# MCU.net
KiCad netlist of a schematic drawn in Altium Designer
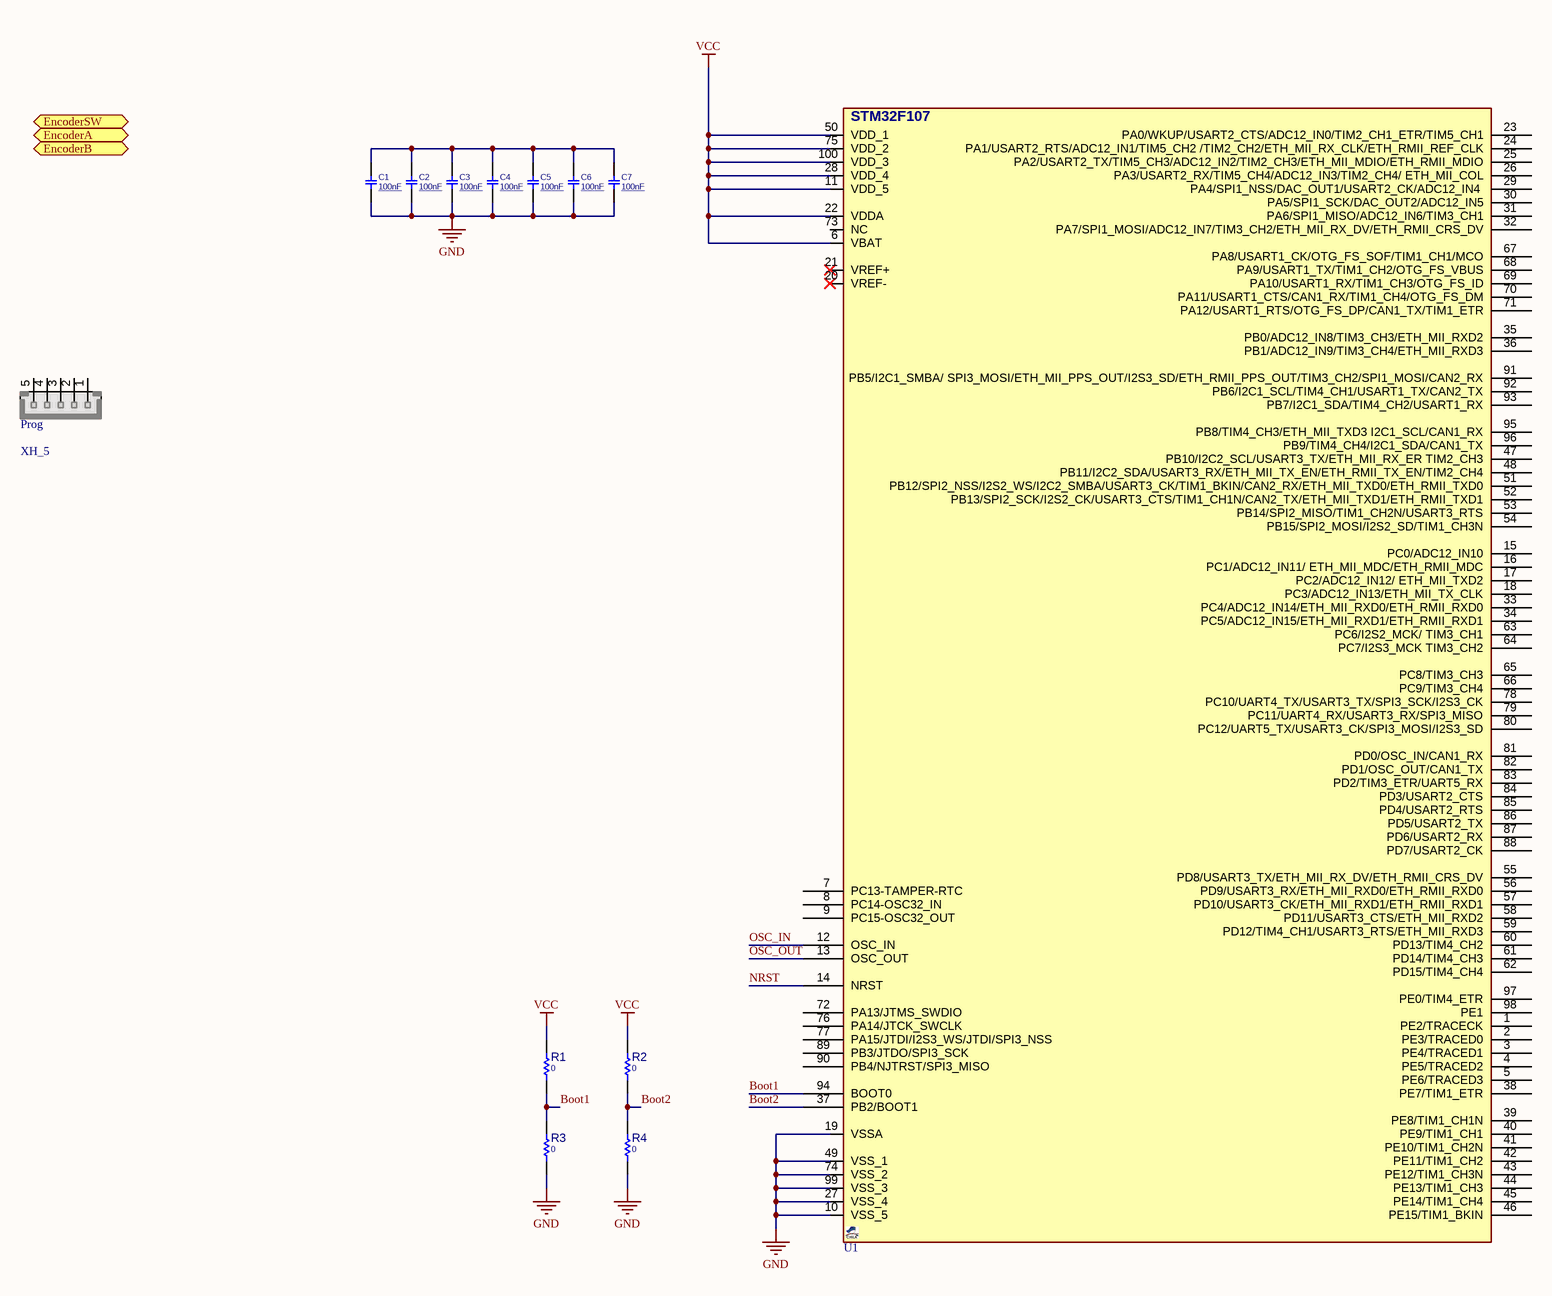
[diagram p0: MCU.SchDoc]

(export (version "E")
  (design (tool "Eeschema 10.0.6"))
  (components
    (comp (ref "C1")
      (value "100nF")
      (footprint "C0805")
      (description "CAP, MLCC, 100nF, 50V,0805")
      (fields (field (name "MANF_P#") "MANF_PART#"))
      (libsource (lib "passive_smd") (part "CAP_SMD_MLCC_0805"))
    )
    (comp (ref "C2")
      (value "100nF")
      (footprint "C0805")
      (description "CAP, MLCC, 100nF, 50V,0805")
      (fields (field (name "MANF_P#") "MANF_PART#"))
      (libsource (lib "passive_smd") (part "CAP_SMD_MLCC_0805"))
    )
    (comp (ref "C3")
      (value "100nF")
      (footprint "C0805")
      (description "CAP, MLCC, 100nF, 50V,0805")
      (fields (field (name "MANF_P#") "MANF_PART#"))
      (libsource (lib "passive_smd") (part "CAP_SMD_MLCC_0805"))
    )
    (comp (ref "C4")
      (value "100nF")
      (footprint "C0805")
      (description "CAP, MLCC, 100nF, 50V,0805")
      (fields (field (name "MANF_P#") "MANF_PART#"))
      (libsource (lib "passive_smd") (part "CAP_SMD_MLCC_0805"))
    )
    (comp (ref "C5")
      (value "100nF")
      (footprint "C0805")
      (description "CAP, MLCC, 100nF, 50V,0805")
      (fields (field (name "MANF_P#") "MANF_PART#"))
      (libsource (lib "passive_smd") (part "CAP_SMD_MLCC_0805"))
    )
    (comp (ref "C6")
      (value "100nF")
      (footprint "C0805")
      (description "CAP, MLCC, 100nF, 50V,0805")
      (fields (field (name "MANF_P#") "MANF_PART#"))
      (libsource (lib "passive_smd") (part "CAP_SMD_MLCC_0805"))
    )
    (comp (ref "C7")
      (value "100nF")
      (footprint "C0805")
      (description "CAP, MLCC, 100nF, 50V,0805")
      (fields (field (name "MANF_P#") "MANF_PART#"))
      (libsource (lib "passive_smd") (part "CAP_SMD_MLCC_0805"))
    )
    (comp (ref "Prog")
      (value "XH_5")
      (footprint "XH_5")
      (description "JST-XH pitch: 2.5mm")
      (fields (field (name "MANF_P#") "JST-B5B-XHA") (field (name "MANF") "JST"))
      (libsource (lib "conn_wire2board") (part "XH_5"))
    )
    (comp (ref "R1")
      (value "0")
      (footprint "R0805")
      (description "RESISTOR, SMD")
      (libsource (lib "passive_smd") (part "RES_SMD_0805"))
    )
    (comp (ref "R2")
      (value "0")
      (footprint "R0805")
      (description "RESISTOR, SMD")
      (libsource (lib "passive_smd") (part "RES_SMD_0805"))
    )
    (comp (ref "R3")
      (value "0")
      (footprint "R0805")
      (description "RESISTOR, SMD")
      (libsource (lib "passive_smd") (part "RES_SMD_0805"))
    )
    (comp (ref "R4")
      (value "0")
      (footprint "R0805")
      (description "RESISTOR, SMD")
      (libsource (lib "passive_smd") (part "RES_SMD_0805"))
    )
    (comp (ref "U1")
      (value "STM32F107")
      (footprint "QFG50_100")
      (description "MCU, STM32 ARM 32-bit, Cortex M3, 256KB FLASH, 64KB SRAM")
      (fields (field (name "MANF") "ST") (field (name "MANF_P#") "STM32F107VBT6"))
      (libsource (lib "mcu_stm32") (part "STM32F107VBT6_QFP100"))
    )
  )
  (nets
    (net (code "1") (name "/Boot1") (class "Default")
      (node (ref "R1") (pin "1") (pinfunction "1_1") (pintype "passive"))
      (node (ref "R3") (pin "2") (pinfunction "2_2") (pintype "passive"))
      (node (ref "U1") (pin "94") (pinfunction "BOOT0_94") (pintype "passive"))
    )
    (net (code "2") (name "/Boot2") (class "Default")
      (node (ref "R2") (pin "1") (pinfunction "1_1") (pintype "passive"))
      (node (ref "R4") (pin "2") (pinfunction "2_2") (pintype "passive"))
      (node (ref "U1") (pin "37") (pinfunction "PB2/BOOT1_37") (pintype "passive"))
    )
    (net (code "6") (name "/NRST") (class "Default")
      (node (ref "U1") (pin "14") (pinfunction "NRST_14") (pintype "passive"))
    )
    (net (code "7") (name "/OSC_IN") (class "Default")
      (node (ref "U1") (pin "12") (pinfunction "OSC_IN_12") (pintype "passive"))
    )
    (net (code "8") (name "/OSC_OUT") (class "Default")
      (node (ref "U1") (pin "13") (pinfunction "OSC_OUT_13") (pintype "passive"))
    )
    (net (code "9") (name "GND") (class "Default")
      (node (ref "C1") (pin "2") (pinfunction "2_2") (pintype "passive"))
      (node (ref "C2") (pin "2") (pinfunction "2_2") (pintype "passive"))
      (node (ref "C3") (pin "2") (pinfunction "2_2") (pintype "passive"))
      (node (ref "C4") (pin "2") (pinfunction "2_2") (pintype "passive"))
      (node (ref "C5") (pin "2") (pinfunction "2_2") (pintype "passive"))
      (node (ref "C6") (pin "2") (pinfunction "2_2") (pintype "passive"))
      (node (ref "C7") (pin "2") (pinfunction "2_2") (pintype "passive"))
      (node (ref "R3") (pin "1") (pinfunction "1_1") (pintype "passive"))
      (node (ref "R4") (pin "1") (pinfunction "1_1") (pintype "passive"))
      (node (ref "U1") (pin "10") (pinfunction "VSS_5_10") (pintype "passive"))
      (node (ref "U1") (pin "19") (pinfunction "VSSA_19") (pintype "passive"))
      (node (ref "U1") (pin "27") (pinfunction "VSS_4_27") (pintype "passive"))
      (node (ref "U1") (pin "49") (pinfunction "VSS_1_49") (pintype "passive"))
      (node (ref "U1") (pin "74") (pinfunction "VSS_2_74") (pintype "passive"))
      (node (ref "U1") (pin "99") (pinfunction "VSS_3_99") (pintype "passive"))
    )
    (net (code "10") (name "Net-(C1-Pad1)") (class "Default")
      (node (ref "C1") (pin "1") (pinfunction "1_1") (pintype "passive"))
      (node (ref "C2") (pin "1") (pinfunction "1_1") (pintype "passive"))
      (node (ref "C3") (pin "1") (pinfunction "1_1") (pintype "passive"))
      (node (ref "C4") (pin "1") (pinfunction "1_1") (pintype "passive"))
      (node (ref "C5") (pin "1") (pinfunction "1_1") (pintype "passive"))
      (node (ref "C6") (pin "1") (pinfunction "1_1") (pintype "passive"))
      (node (ref "C7") (pin "1") (pinfunction "1_1") (pintype "passive"))
    )
    (net (code "11") (name "VCC") (class "Default")
      (node (ref "R1") (pin "2") (pinfunction "2_2") (pintype "passive"))
      (node (ref "R2") (pin "2") (pinfunction "2_2") (pintype "passive"))
      (node (ref "U1") (pin "100") (pinfunction "VDD_3_100") (pintype "passive"))
      (node (ref "U1") (pin "11") (pinfunction "VDD_5_11") (pintype "passive"))
      (node (ref "U1") (pin "22") (pinfunction "VDDA_22") (pintype "passive"))
      (node (ref "U1") (pin "28") (pinfunction "VDD_4_28") (pintype "passive"))
      (node (ref "U1") (pin "50") (pinfunction "VDD_1_50") (pintype "passive"))
      (node (ref "U1") (pin "6") (pinfunction "VBAT_6") (pintype "passive"))
      (node (ref "U1") (pin "75") (pinfunction "VDD_2_75") (pintype "passive"))
    )
    (net (code "12") (name "unconnected-(Prog-Pad1)") (class "Default")
      (node (ref "Prog") (pin "1") (pinfunction "1_1") (pintype "passive"))
    )
    (net (code "13") (name "unconnected-(Prog-Pad2)") (class "Default")
      (node (ref "Prog") (pin "2") (pinfunction "2_2") (pintype "passive"))
    )
    (net (code "14") (name "unconnected-(Prog-Pad3)") (class "Default")
      (node (ref "Prog") (pin "3") (pinfunction "3_3") (pintype "passive"))
    )
    (net (code "15") (name "unconnected-(Prog-Pad4)") (class "Default")
      (node (ref "Prog") (pin "4") (pinfunction "4_4") (pintype "passive"))
    )
    (net (code "16") (name "unconnected-(Prog-Pad5)") (class "Default")
      (node (ref "Prog") (pin "5") (pinfunction "5_5") (pintype "passive"))
    )
    (net (code "17") (name "unconnected-(U1-NC-Pad73)") (class "Default")
      (node (ref "U1") (pin "73") (pinfunction "NC_73") (pintype "passive"))
    )
    (net (code "18") (name "unconnected-(U1-PA0{slash}WKUP{slash}USART2_CTS{slash}ADC12_IN0{slash}TIM2_CH1_ETR{slash}TIM5_CH1-Pad23)") (class "Default")
      (node (ref "U1") (pin "23") (pinfunction "PA0/WKUP/USART2_CTS/ADC12_IN0/TIM2_CH1_ETR/TIM5_CH1_23") (pintype "passive"))
    )
    (net (code "19") (name "unconnected-(U1-PA1{slash}USART2_RTS{slash}ADC12_IN1{slash}TIM5_CH2_{slash}TIM2_CH2{slash}ETH_MII_RX_CLK{slash}ETH_RMII_REF_CLK-Pad24)") (class "Default")
      (node (ref "U1") (pin "24") (pinfunction "PA1/USART2_RTS/ADC12_IN1/TIM5_CH2_/TIM2_CH2/ETH_MII_RX_CLK/ETH_RMII_REF_CLK_24") (pintype "passive"))
    )
    (net (code "20") (name "unconnected-(U1-PA2{slash}USART2_TX{slash}TIM5_CH3{slash}ADC12_IN2{slash}TIM2_CH3{slash}ETH_MII_MDIO{slash}ETH_RMII_MDIO-Pad25)") (class "Default")
      (node (ref "U1") (pin "25") (pinfunction "PA2/USART2_TX/TIM5_CH3/ADC12_IN2/TIM2_CH3/ETH_MII_MDIO/ETH_RMII_MDIO_25") (pintype "passive"))
    )
    (net (code "21") (name "unconnected-(U1-PA3{slash}USART2_RX{slash}TIM5_CH4{slash}ADC12_IN3{slash}TIM2_CH4{slash}_ETH_MII_COL-Pad26)") (class "Default")
      (node (ref "U1") (pin "26") (pinfunction "PA3/USART2_RX/TIM5_CH4/ADC12_IN3/TIM2_CH4/_ETH_MII_COL_26") (pintype "passive"))
    )
    (net (code "22") (name "unconnected-(U1-PA4{slash}SPI1_NSS{slash}DAC_OUT1{slash}USART2_CK{slash}ADC12_IN4-Pad29)") (class "Default")
      (node (ref "U1") (pin "29") (pinfunction "PA4/SPI1_NSS/DAC_OUT1/USART2_CK/ADC12_IN4_29") (pintype "passive"))
    )
    (net (code "23") (name "unconnected-(U1-PA5{slash}SPI1_SCK{slash}DAC_OUT2{slash}ADC12_IN5-Pad30)") (class "Default")
      (node (ref "U1") (pin "30") (pinfunction "PA5/SPI1_SCK/DAC_OUT2/ADC12_IN5_30") (pintype "passive"))
    )
    (net (code "24") (name "unconnected-(U1-PA6{slash}SPI1_MISO{slash}ADC12_IN6{slash}TIM3_CH1-Pad31)") (class "Default")
      (node (ref "U1") (pin "31") (pinfunction "PA6/SPI1_MISO/ADC12_IN6/TIM3_CH1_31") (pintype "passive"))
    )
    (net (code "25") (name "unconnected-(U1-PA7{slash}SPI1_MOSI{slash}ADC12_IN7{slash}TIM3_CH2{slash}ETH_MII_RX_DV{slash}ETH_RMII_CRS_DV-Pad32)") (class "Default")
      (node (ref "U1") (pin "32") (pinfunction "PA7/SPI1_MOSI/ADC12_IN7/TIM3_CH2/ETH_MII_RX_DV/ETH_RMII_CRS_DV_32") (pintype "passive"))
    )
    (net (code "26") (name "unconnected-(U1-PA8{slash}USART1_CK{slash}OTG_FS_SOF{slash}TIM1_CH1{slash}MCO-Pad67)") (class "Default")
      (node (ref "U1") (pin "67") (pinfunction "PA8/USART1_CK/OTG_FS_SOF/TIM1_CH1/MCO_67") (pintype "passive"))
    )
    (net (code "27") (name "unconnected-(U1-PA9{slash}USART1_TX{slash}TIM1_CH2{slash}OTG_FS_VBUS-Pad68)") (class "Default")
      (node (ref "U1") (pin "68") (pinfunction "PA9/USART1_TX/TIM1_CH2/OTG_FS_VBUS_68") (pintype "passive"))
    )
    (net (code "28") (name "unconnected-(U1-PA10{slash}USART1_RX{slash}TIM1_CH3{slash}OTG_FS_ID-Pad69)") (class "Default")
      (node (ref "U1") (pin "69") (pinfunction "PA10/USART1_RX/TIM1_CH3/OTG_FS_ID_69") (pintype "passive"))
    )
    (net (code "29") (name "unconnected-(U1-PA11{slash}USART1_CTS{slash}CAN1_RX{slash}TIM1_CH4{slash}OTG_FS_DM-Pad70)") (class "Default")
      (node (ref "U1") (pin "70") (pinfunction "PA11/USART1_CTS/CAN1_RX/TIM1_CH4/OTG_FS_DM_70") (pintype "passive"))
    )
    (net (code "30") (name "unconnected-(U1-PA12{slash}USART1_RTS{slash}OTG_FS_DP{slash}CAN1_TX{slash}TIM1_ETR-Pad71)") (class "Default")
      (node (ref "U1") (pin "71") (pinfunction "PA12/USART1_RTS/OTG_FS_DP/CAN1_TX/TIM1_ETR_71") (pintype "passive"))
    )
    (net (code "31") (name "unconnected-(U1-PA13{slash}JTMS_SWDIO-Pad72)") (class "Default")
      (node (ref "U1") (pin "72") (pinfunction "PA13/JTMS_SWDIO_72") (pintype "passive"))
    )
    (net (code "32") (name "unconnected-(U1-PA14{slash}JTCK_SWCLK-Pad76)") (class "Default")
      (node (ref "U1") (pin "76") (pinfunction "PA14/JTCK_SWCLK_76") (pintype "passive"))
    )
    (net (code "33") (name "unconnected-(U1-PA15{slash}JTDI{slash}I2S3_WS{slash}JTDI{slash}SPI3_NSS-Pad77)") (class "Default")
      (node (ref "U1") (pin "77") (pinfunction "PA15/JTDI/I2S3_WS/JTDI/SPI3_NSS_77") (pintype "passive"))
    )
    (net (code "34") (name "unconnected-(U1-PB0{slash}ADC12_IN8{slash}TIM3_CH3{slash}ETH_MII_RXD2-Pad35)") (class "Default")
      (node (ref "U1") (pin "35") (pinfunction "PB0/ADC12_IN8/TIM3_CH3/ETH_MII_RXD2_35") (pintype "passive"))
    )
    (net (code "35") (name "unconnected-(U1-PB1{slash}ADC12_IN9{slash}TIM3_CH4{slash}ETH_MII_RXD3-Pad36)") (class "Default")
      (node (ref "U1") (pin "36") (pinfunction "PB1/ADC12_IN9/TIM3_CH4/ETH_MII_RXD3_36") (pintype "passive"))
    )
    (net (code "36") (name "unconnected-(U1-PB3{slash}JTDO{slash}SPI3_SCK-Pad89)") (class "Default")
      (node (ref "U1") (pin "89") (pinfunction "PB3/JTDO/SPI3_SCK_89") (pintype "passive"))
    )
    (net (code "37") (name "unconnected-(U1-PB4{slash}NJTRST{slash}SPI3_MISO-Pad90)") (class "Default")
      (node (ref "U1") (pin "90") (pinfunction "PB4/NJTRST/SPI3_MISO_90") (pintype "passive"))
    )
    (net (code "38") (name "unconnected-(U1-PB5{slash}I2C1_SMBA{slash}_SPI3_MOSI{slash}ETH_MII_PPS_OUT{slash}I2S3_SD{slash}ETH_RMII_PPS_OUT{slash}TIM3_CH2{slash}SPI1_MOSI{slash}CAN2_RX-Pad91)") (class "Default")
      (node (ref "U1") (pin "91") (pinfunction "PB5/I2C1_SMBA/_SPI3_MOSI/ETH_MII_PPS_OUT/I2S3_SD/ETH_RMII_PPS_OUT/TIM3_CH2/SPI1_MOSI/CAN2_RX_91") (pintype "passive"))
    )
    (net (code "39") (name "unconnected-(U1-PB6{slash}I2C1_SCL{slash}TIM4_CH1{slash}USART1_TX{slash}CAN2_TX-Pad92)") (class "Default")
      (node (ref "U1") (pin "92") (pinfunction "PB6/I2C1_SCL/TIM4_CH1/USART1_TX/CAN2_TX_92") (pintype "passive"))
    )
    (net (code "40") (name "unconnected-(U1-PB7{slash}I2C1_SDA{slash}TIM4_CH2{slash}USART1_RX-Pad93)") (class "Default")
      (node (ref "U1") (pin "93") (pinfunction "PB7/I2C1_SDA/TIM4_CH2/USART1_RX_93") (pintype "passive"))
    )
    (net (code "41") (name "unconnected-(U1-PB8{slash}TIM4_CH3{slash}ETH_MII_TXD3_I2C1_SCL{slash}CAN1_RX-Pad95)") (class "Default")
      (node (ref "U1") (pin "95") (pinfunction "PB8/TIM4_CH3/ETH_MII_TXD3_I2C1_SCL/CAN1_RX_95") (pintype "passive"))
    )
    (net (code "42") (name "unconnected-(U1-PB9{slash}TIM4_CH4{slash}I2C1_SDA{slash}CAN1_TX-Pad96)") (class "Default")
      (node (ref "U1") (pin "96") (pinfunction "PB9/TIM4_CH4/I2C1_SDA/CAN1_TX_96") (pintype "passive"))
    )
    (net (code "43") (name "unconnected-(U1-PB10{slash}I2C2_SCL{slash}USART3_TX{slash}ETH_MII_RX_ER_TIM2_CH3-Pad47)") (class "Default")
      (node (ref "U1") (pin "47") (pinfunction "PB10/I2C2_SCL/USART3_TX/ETH_MII_RX_ER_TIM2_CH3_47") (pintype "passive"))
    )
    (net (code "44") (name "unconnected-(U1-PB11{slash}I2C2_SDA{slash}USART3_RX{slash}ETH_MII_TX_EN{slash}ETH_RMII_TX_EN{slash}TIM2_CH4-Pad48)") (class "Default")
      (node (ref "U1") (pin "48") (pinfunction "PB11/I2C2_SDA/USART3_RX/ETH_MII_TX_EN/ETH_RMII_TX_EN/TIM2_CH4_48") (pintype "passive"))
    )
    (net (code "45") (name "unconnected-(U1-PB12{slash}SPI2_NSS{slash}I2S2_WS{slash}I2C2_SMBA{slash}USART3_CK{slash}TIM1_BKIN{slash}CAN2_RX{slash}ETH_MII_TXD0{slash}ETH_RMII_TXD0-Pad51)") (class "Default")
      (node (ref "U1") (pin "51") (pinfunction "PB12/SPI2_NSS/I2S2_WS/I2C2_SMBA/USART3_CK/TIM1_BKIN/CAN2_RX/ETH_MII_TXD0/ETH_RMII_TXD0_51") (pintype "passive"))
    )
    (net (code "46") (name "unconnected-(U1-PB13{slash}SPI2_SCK{slash}I2S2_CK{slash}USART3_CTS{slash}TIM1_CH1N{slash}CAN2_TX{slash}ETH_MII_TXD1{slash}ETH_RMII_TXD1-Pad52)") (class "Default")
      (node (ref "U1") (pin "52") (pinfunction "PB13/SPI2_SCK/I2S2_CK/USART3_CTS/TIM1_CH1N/CAN2_TX/ETH_MII_TXD1/ETH_RMII_TXD1_52") (pintype "passive"))
    )
    (net (code "47") (name "unconnected-(U1-PB14{slash}SPI2_MISO{slash}TIM1_CH2N{slash}USART3_RTS-Pad53)") (class "Default")
      (node (ref "U1") (pin "53") (pinfunction "PB14/SPI2_MISO/TIM1_CH2N/USART3_RTS_53") (pintype "passive"))
    )
    (net (code "48") (name "unconnected-(U1-PB15{slash}SPI2_MOSI{slash}I2S2_SD{slash}TIM1_CH3N-Pad54)") (class "Default")
      (node (ref "U1") (pin "54") (pinfunction "PB15/SPI2_MOSI/I2S2_SD/TIM1_CH3N_54") (pintype "passive"))
    )
    (net (code "49") (name "unconnected-(U1-PC0{slash}ADC12_IN10-Pad15)") (class "Default")
      (node (ref "U1") (pin "15") (pinfunction "PC0/ADC12_IN10_15") (pintype "passive"))
    )
    (net (code "50") (name "unconnected-(U1-PC1{slash}ADC12_IN11{slash}_ETH_MII_MDC{slash}ETH_RMII_MDC-Pad16)") (class "Default")
      (node (ref "U1") (pin "16") (pinfunction "PC1/ADC12_IN11/_ETH_MII_MDC/ETH_RMII_MDC_16") (pintype "passive"))
    )
    (net (code "51") (name "unconnected-(U1-PC2{slash}ADC12_IN12{slash}_ETH_MII_TXD2-Pad17)") (class "Default")
      (node (ref "U1") (pin "17") (pinfunction "PC2/ADC12_IN12/_ETH_MII_TXD2_17") (pintype "passive"))
    )
    (net (code "52") (name "unconnected-(U1-PC3{slash}ADC12_IN13{slash}ETH_MII_TX_CLK-Pad18)") (class "Default")
      (node (ref "U1") (pin "18") (pinfunction "PC3/ADC12_IN13/ETH_MII_TX_CLK_18") (pintype "passive"))
    )
    (net (code "53") (name "unconnected-(U1-PC4{slash}ADC12_IN14{slash}ETH_MII_RXD0{slash}ETH_RMII_RXD0-Pad33)") (class "Default")
      (node (ref "U1") (pin "33") (pinfunction "PC4/ADC12_IN14/ETH_MII_RXD0/ETH_RMII_RXD0_33") (pintype "passive"))
    )
    (net (code "54") (name "unconnected-(U1-PC5{slash}ADC12_IN15{slash}ETH_MII_RXD1{slash}ETH_RMII_RXD1-Pad34)") (class "Default")
      (node (ref "U1") (pin "34") (pinfunction "PC5/ADC12_IN15/ETH_MII_RXD1/ETH_RMII_RXD1_34") (pintype "passive"))
    )
    (net (code "55") (name "unconnected-(U1-PC6{slash}I2S2_MCK{slash}_TIM3_CH1-Pad63)") (class "Default")
      (node (ref "U1") (pin "63") (pinfunction "PC6/I2S2_MCK/_TIM3_CH1_63") (pintype "passive"))
    )
    (net (code "56") (name "unconnected-(U1-PC7{slash}I2S3_MCK_TIM3_CH2-Pad64)") (class "Default")
      (node (ref "U1") (pin "64") (pinfunction "PC7/I2S3_MCK_TIM3_CH2_64") (pintype "passive"))
    )
    (net (code "57") (name "unconnected-(U1-PC8{slash}TIM3_CH3-Pad65)") (class "Default")
      (node (ref "U1") (pin "65") (pinfunction "PC8/TIM3_CH3_65") (pintype "passive"))
    )
    (net (code "58") (name "unconnected-(U1-PC9{slash}TIM3_CH4-Pad66)") (class "Default")
      (node (ref "U1") (pin "66") (pinfunction "PC9/TIM3_CH4_66") (pintype "passive"))
    )
    (net (code "59") (name "unconnected-(U1-PC10{slash}UART4_TX{slash}USART3_TX{slash}SPI3_SCK{slash}I2S3_CK-Pad78)") (class "Default")
      (node (ref "U1") (pin "78") (pinfunction "PC10/UART4_TX/USART3_TX/SPI3_SCK/I2S3_CK_78") (pintype "passive"))
    )
    (net (code "60") (name "unconnected-(U1-PC11{slash}UART4_RX{slash}USART3_RX{slash}SPI3_MISO-Pad79)") (class "Default")
      (node (ref "U1") (pin "79") (pinfunction "PC11/UART4_RX/USART3_RX/SPI3_MISO_79") (pintype "passive"))
    )
    (net (code "61") (name "unconnected-(U1-PC12{slash}UART5_TX{slash}USART3_CK{slash}SPI3_MOSI{slash}I2S3_SD-Pad80)") (class "Default")
      (node (ref "U1") (pin "80") (pinfunction "PC12/UART5_TX/USART3_CK/SPI3_MOSI/I2S3_SD_80") (pintype "passive"))
    )
    (net (code "62") (name "unconnected-(U1-PC13-TAMPER-RTC-Pad7)") (class "Default")
      (node (ref "U1") (pin "7") (pinfunction "PC13-TAMPER-RTC_7") (pintype "passive"))
    )
    (net (code "63") (name "unconnected-(U1-PC14-OSC32_IN-Pad8)") (class "Default")
      (node (ref "U1") (pin "8") (pinfunction "PC14-OSC32_IN_8") (pintype "passive"))
    )
    (net (code "64") (name "unconnected-(U1-PC15-OSC32_OUT-Pad9)") (class "Default")
      (node (ref "U1") (pin "9") (pinfunction "PC15-OSC32_OUT_9") (pintype "passive"))
    )
    (net (code "65") (name "unconnected-(U1-PD0{slash}OSC_IN{slash}CAN1_RX-Pad81)") (class "Default")
      (node (ref "U1") (pin "81") (pinfunction "PD0/OSC_IN/CAN1_RX_81") (pintype "passive"))
    )
    (net (code "66") (name "unconnected-(U1-PD1{slash}OSC_OUT{slash}CAN1_TX-Pad82)") (class "Default")
      (node (ref "U1") (pin "82") (pinfunction "PD1/OSC_OUT/CAN1_TX_82") (pintype "passive"))
    )
    (net (code "67") (name "unconnected-(U1-PD2{slash}TIM3_ETR{slash}UART5_RX-Pad83)") (class "Default")
      (node (ref "U1") (pin "83") (pinfunction "PD2/TIM3_ETR/UART5_RX_83") (pintype "passive"))
    )
    (net (code "68") (name "unconnected-(U1-PD3{slash}USART2_CTS-Pad84)") (class "Default")
      (node (ref "U1") (pin "84") (pinfunction "PD3/USART2_CTS_84") (pintype "passive"))
    )
    (net (code "69") (name "unconnected-(U1-PD4{slash}USART2_RTS-Pad85)") (class "Default")
      (node (ref "U1") (pin "85") (pinfunction "PD4/USART2_RTS_85") (pintype "passive"))
    )
    (net (code "70") (name "unconnected-(U1-PD5{slash}USART2_TX-Pad86)") (class "Default")
      (node (ref "U1") (pin "86") (pinfunction "PD5/USART2_TX_86") (pintype "passive"))
    )
    (net (code "71") (name "unconnected-(U1-PD6{slash}USART2_RX-Pad87)") (class "Default")
      (node (ref "U1") (pin "87") (pinfunction "PD6/USART2_RX_87") (pintype "passive"))
    )
    (net (code "72") (name "unconnected-(U1-PD7{slash}USART2_CK-Pad88)") (class "Default")
      (node (ref "U1") (pin "88") (pinfunction "PD7/USART2_CK_88") (pintype "passive"))
    )
    (net (code "73") (name "unconnected-(U1-PD8{slash}USART3_TX{slash}ETH_MII_RX_DV{slash}ETH_RMII_CRS_DV-Pad55)") (class "Default")
      (node (ref "U1") (pin "55") (pinfunction "PD8/USART3_TX/ETH_MII_RX_DV/ETH_RMII_CRS_DV_55") (pintype "passive"))
    )
    (net (code "74") (name "unconnected-(U1-PD9{slash}USART3_RX{slash}ETH_MII_RXD0{slash}ETH_RMII_RXD0-Pad56)") (class "Default")
      (node (ref "U1") (pin "56") (pinfunction "PD9/USART3_RX/ETH_MII_RXD0/ETH_RMII_RXD0_56") (pintype "passive"))
    )
    (net (code "75") (name "unconnected-(U1-PD10{slash}USART3_CK{slash}ETH_MII_RXD1{slash}ETH_RMII_RXD1-Pad57)") (class "Default")
      (node (ref "U1") (pin "57") (pinfunction "PD10/USART3_CK/ETH_MII_RXD1/ETH_RMII_RXD1_57") (pintype "passive"))
    )
    (net (code "76") (name "unconnected-(U1-PD11{slash}USART3_CTS{slash}ETH_MII_RXD2-Pad58)") (class "Default")
      (node (ref "U1") (pin "58") (pinfunction "PD11/USART3_CTS/ETH_MII_RXD2_58") (pintype "passive"))
    )
    (net (code "77") (name "unconnected-(U1-PD12{slash}TIM4_CH1{slash}USART3_RTS{slash}ETH_MII_RXD3-Pad59)") (class "Default")
      (node (ref "U1") (pin "59") (pinfunction "PD12/TIM4_CH1/USART3_RTS/ETH_MII_RXD3_59") (pintype "passive"))
    )
    (net (code "78") (name "unconnected-(U1-PD13{slash}TIM4_CH2-Pad60)") (class "Default")
      (node (ref "U1") (pin "60") (pinfunction "PD13/TIM4_CH2_60") (pintype "passive"))
    )
    (net (code "79") (name "unconnected-(U1-PD14{slash}TIM4_CH3-Pad61)") (class "Default")
      (node (ref "U1") (pin "61") (pinfunction "PD14/TIM4_CH3_61") (pintype "passive"))
    )
    (net (code "80") (name "unconnected-(U1-PD15{slash}TIM4_CH4-Pad62)") (class "Default")
      (node (ref "U1") (pin "62") (pinfunction "PD15/TIM4_CH4_62") (pintype "passive"))
    )
    (net (code "81") (name "unconnected-(U1-PE0{slash}TIM4_ETR-Pad97)") (class "Default")
      (node (ref "U1") (pin "97") (pinfunction "PE0/TIM4_ETR_97") (pintype "passive"))
    )
    (net (code "82") (name "unconnected-(U1-PE1-Pad98)") (class "Default")
      (node (ref "U1") (pin "98") (pinfunction "PE1_98") (pintype "passive"))
    )
    (net (code "83") (name "unconnected-(U1-PE2{slash}TRACECK-Pad1)") (class "Default")
      (node (ref "U1") (pin "1") (pinfunction "PE2/TRACECK_1") (pintype "passive"))
    )
    (net (code "84") (name "unconnected-(U1-PE3{slash}TRACED0-Pad2)") (class "Default")
      (node (ref "U1") (pin "2") (pinfunction "PE3/TRACED0_2") (pintype "passive"))
    )
    (net (code "85") (name "unconnected-(U1-PE4{slash}TRACED1-Pad3)") (class "Default")
      (node (ref "U1") (pin "3") (pinfunction "PE4/TRACED1_3") (pintype "passive"))
    )
    (net (code "86") (name "unconnected-(U1-PE5{slash}TRACED2-Pad4)") (class "Default")
      (node (ref "U1") (pin "4") (pinfunction "PE5/TRACED2_4") (pintype "passive"))
    )
    (net (code "87") (name "unconnected-(U1-PE6{slash}TRACED3-Pad5)") (class "Default")
      (node (ref "U1") (pin "5") (pinfunction "PE6/TRACED3_5") (pintype "passive"))
    )
    (net (code "88") (name "unconnected-(U1-PE7{slash}TIM1_ETR-Pad38)") (class "Default")
      (node (ref "U1") (pin "38") (pinfunction "PE7/TIM1_ETR_38") (pintype "passive"))
    )
    (net (code "89") (name "unconnected-(U1-PE8{slash}TIM1_CH1N-Pad39)") (class "Default")
      (node (ref "U1") (pin "39") (pinfunction "PE8/TIM1_CH1N_39") (pintype "passive"))
    )
    (net (code "90") (name "unconnected-(U1-PE9{slash}TIM1_CH1-Pad40)") (class "Default")
      (node (ref "U1") (pin "40") (pinfunction "PE9/TIM1_CH1_40") (pintype "passive"))
    )
    (net (code "91") (name "unconnected-(U1-PE10{slash}TIM1_CH2N-Pad41)") (class "Default")
      (node (ref "U1") (pin "41") (pinfunction "PE10/TIM1_CH2N_41") (pintype "passive"))
    )
    (net (code "92") (name "unconnected-(U1-PE11{slash}TIM1_CH2-Pad42)") (class "Default")
      (node (ref "U1") (pin "42") (pinfunction "PE11/TIM1_CH2_42") (pintype "passive"))
    )
    (net (code "93") (name "unconnected-(U1-PE12{slash}TIM1_CH3N-Pad43)") (class "Default")
      (node (ref "U1") (pin "43") (pinfunction "PE12/TIM1_CH3N_43") (pintype "passive"))
    )
    (net (code "94") (name "unconnected-(U1-PE13{slash}TIM1_CH3-Pad44)") (class "Default")
      (node (ref "U1") (pin "44") (pinfunction "PE13/TIM1_CH3_44") (pintype "passive"))
    )
    (net (code "95") (name "unconnected-(U1-PE14{slash}TIM1_CH4-Pad45)") (class "Default")
      (node (ref "U1") (pin "45") (pinfunction "PE14/TIM1_CH4_45") (pintype "passive"))
    )
    (net (code "96") (name "unconnected-(U1-PE15{slash}TIM1_BKIN-Pad46)") (class "Default")
      (node (ref "U1") (pin "46") (pinfunction "PE15/TIM1_BKIN_46") (pintype "passive"))
    )
    (net (code "97") (name "unconnected-(U1-VREF+-Pad21)") (class "Default")
      (node (ref "U1") (pin "21") (pinfunction "VREF+_21") (pintype "passive+no_connect"))
    )
    (net (code "98") (name "unconnected-(U1-VREF--Pad20)") (class "Default")
      (node (ref "U1") (pin "20") (pinfunction "VREF-_20") (pintype "passive+no_connect"))
    )
  )
)
